# boost_0_8V_to_3_3V_v0_1.net
KiCad netlist of a schematic drawn in EasyEDA Pro
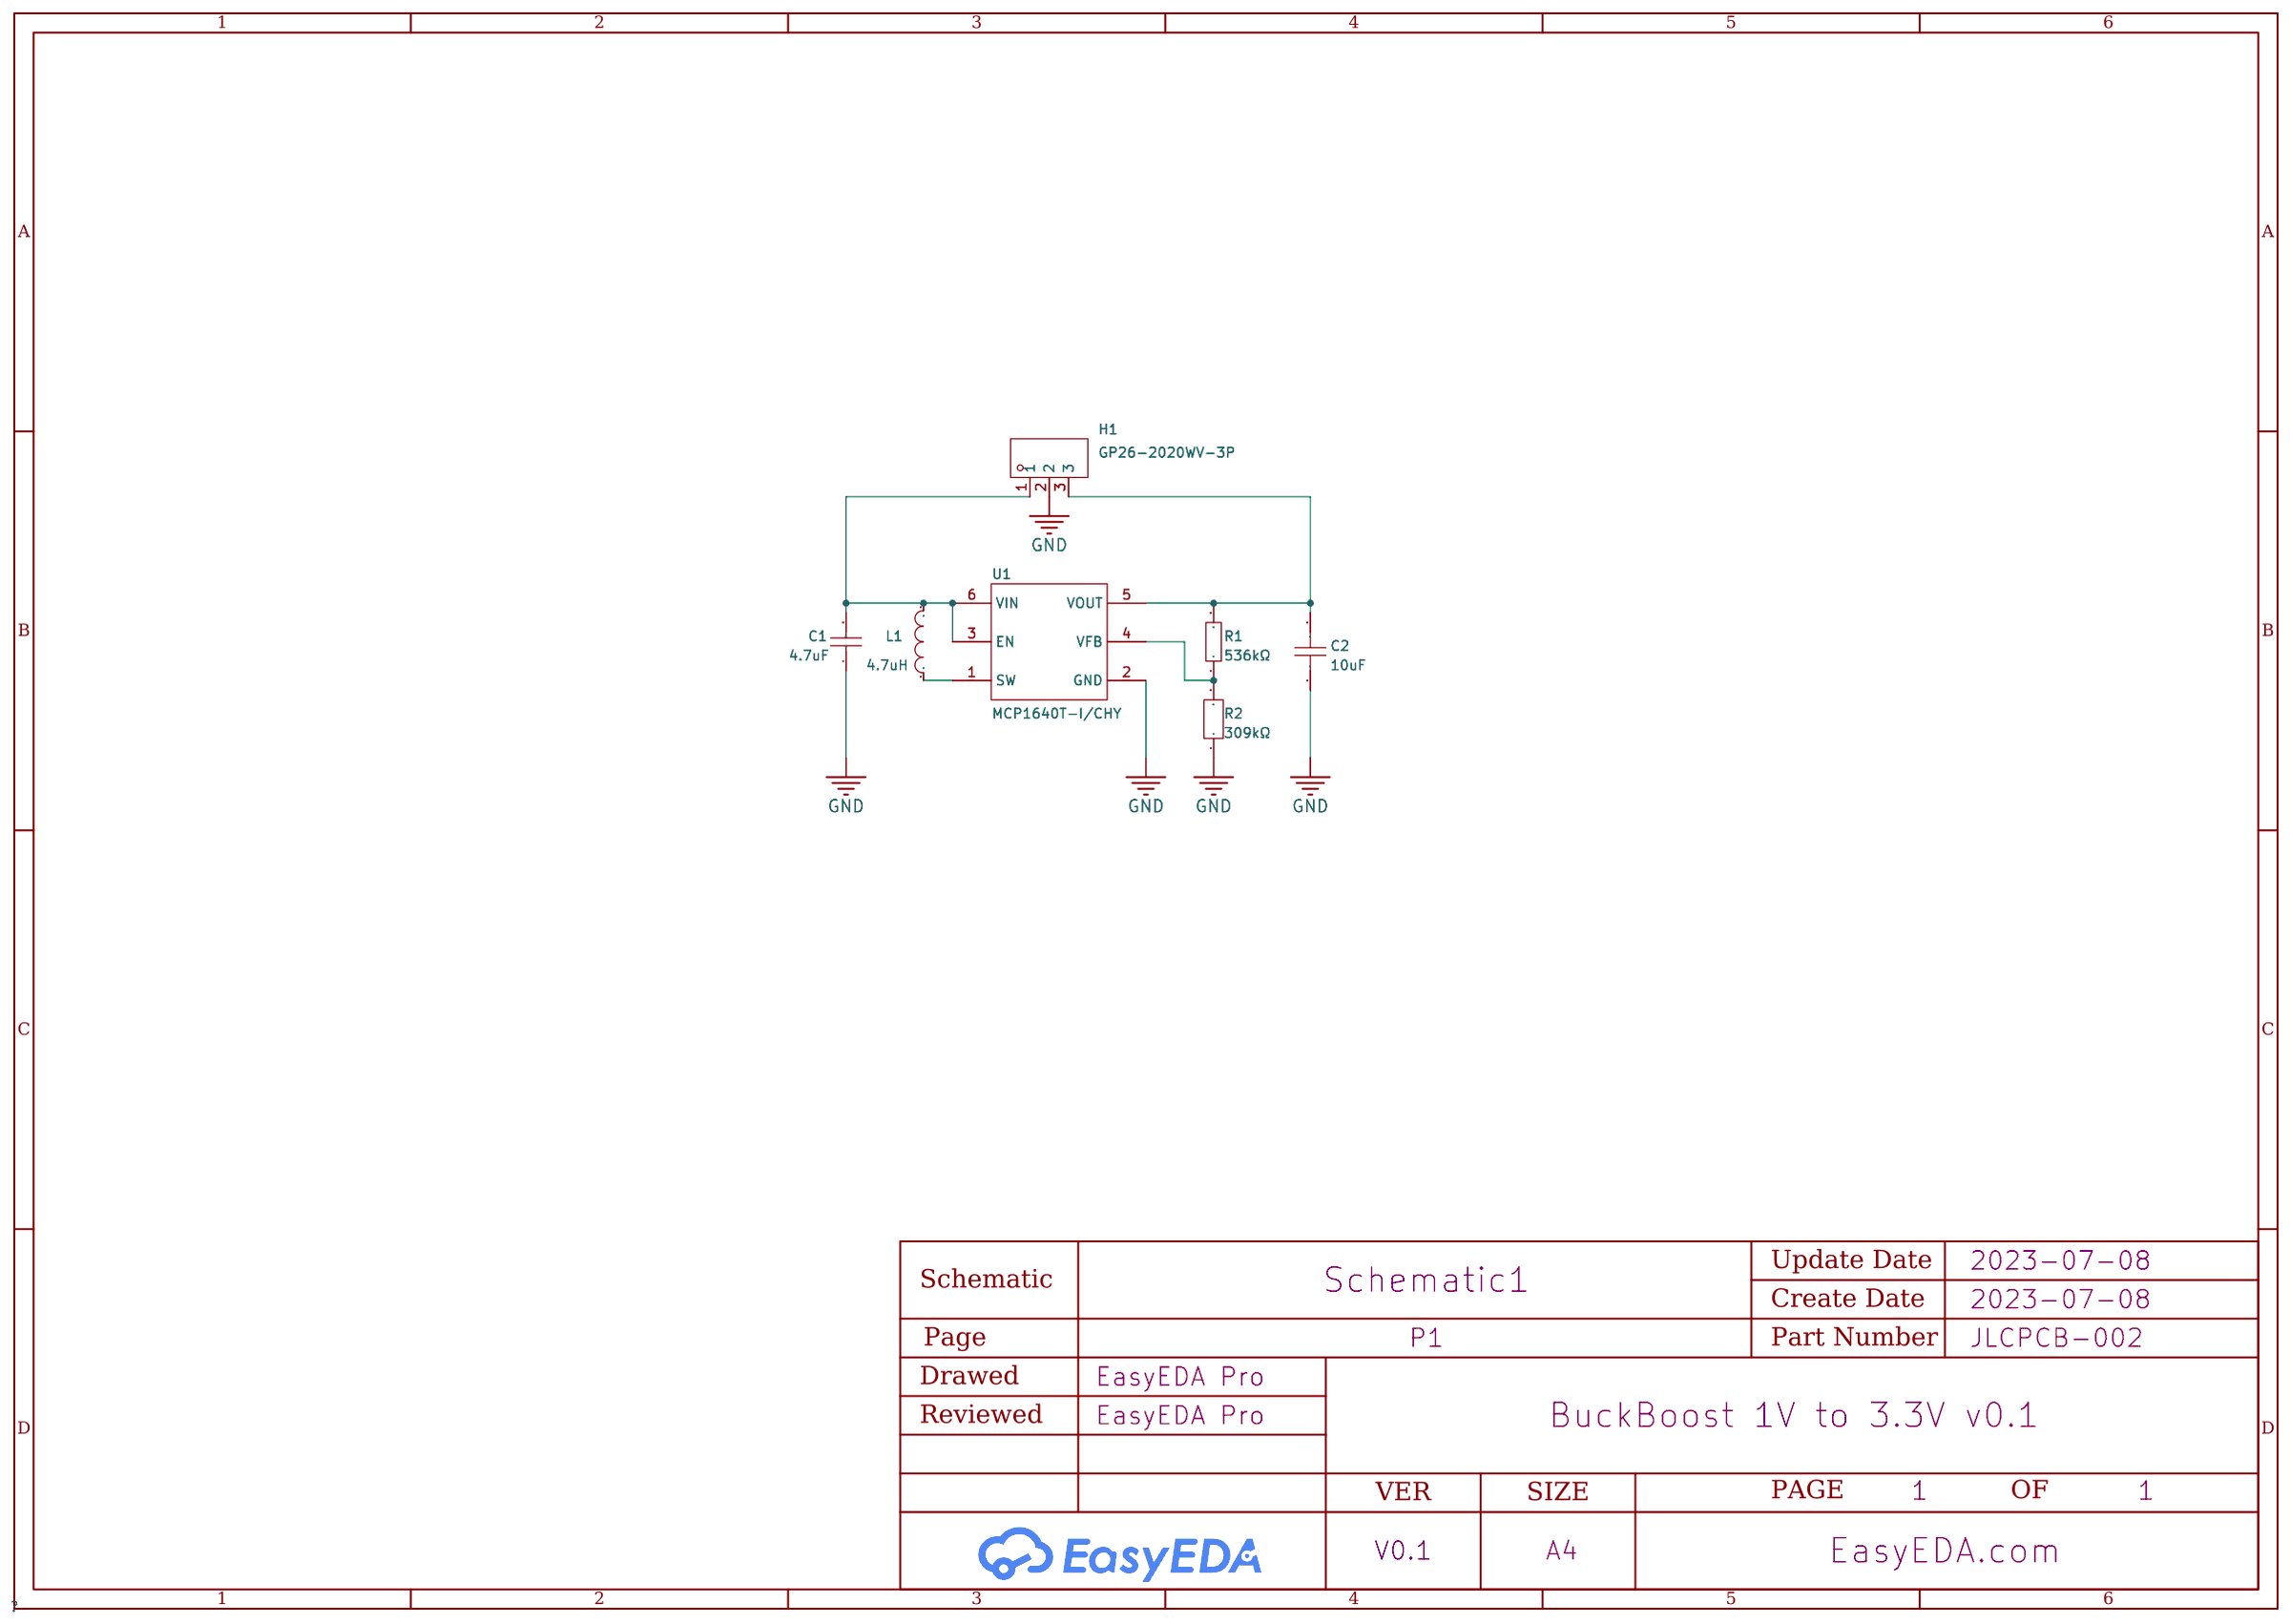
[diagram p0: schematic sheet]

(export (version "E")
  (design (tool "Eeschema 10.0.6"))
  (components
    (comp (ref "C1")
      (value "4.7uF")
      (footprint "easyedapro:C0603")
      (fields
        (field (name "Manufacturer Part") "CL10A475KO8NNNC")
        (field (name "Manufacturer") "SAMSUNG(三星)")
      )
      (libsource (lib "easyedapro") (part "CL10A475KO8NNNC"))
    )
    (comp (ref "C2")
      (value "10uF")
      (footprint "easyedapro:C0603")
      (fields
        (field (name "Manufacturer Part") "CL10A106KP8NNNC")
        (field (name "Manufacturer") "SAMSUNG(三星)")
      )
      (libsource (lib "easyedapro") (part "CL10A106KP8NNNC"))
    )
    (comp (ref "H1")
      (value "GP26-2020WV-3P")
      (footprint "easyedapro:HDR-TH_3P-P2.00-V-M")
      (fields (field (name "Manufacturer") "GEPU(歌普)"))
      (libsource (lib "easyedapro") (part "GP26-2020WV-3P"))
    )
    (comp (ref "L1")
      (value "4.7uH")
      (footprint "easyedapro:IND-SMD_L2.5-W1.8")
      (fields
        (field (name "Manufacturer Part") "CBC2518T4R7M")
        (field (name "Manufacturer") "TAIYO YUDEN(太诱)")
      )
      (libsource (lib "easyedapro") (part "CBC2518T4R7M"))
    )
    (comp (ref "R1")
      (value "536kΩ")
      (footprint "easyedapro:R0603")
      (fields (field (name "Manufacturer Part") "RTT035363FTP") (field (name "Manufacturer") "RALEC(旺诠)"))
      (libsource (lib "easyedapro") (part "RTT035363FTP"))
    )
    (comp (ref "R2")
      (value "309kΩ")
      (footprint "easyedapro:R0603")
      (fields (field (name "Manufacturer Part") "TD03G3093BT") (field (name "Manufacturer") "FH(风华)"))
      (libsource (lib "easyedapro") (part "TD03G3093BT"))
    )
    (comp (ref "U1")
      (value "MCP1640T-I/CHY")
      (footprint "easyedapro:SOT-23-6_L2.9-W1.6-P0.95-LS2.8-BR")
      (fields (field (name "Manufacturer") "MICROCHIP(美国微芯)"))
      (libsource (lib "easyedapro") (part "MCP1640T-I/CHY"))
    )
  )
  (nets
    (net (code "1") (name "GND") (class "Default")
      (node (ref "C1") (pin "1") (pinfunction "1_1") (pintype "input"))
      (node (ref "C2") (pin "1") (pinfunction "1_1") (pintype "input"))
      (node (ref "H1") (pin "2") (pinfunction "2_2") (pintype "input"))
      (node (ref "R2") (pin "1") (pinfunction "1_1") (pintype "input"))
      (node (ref "U1") (pin "2") (pinfunction "GND_2") (pintype "input"))
    )
    (net (code "2") (name "Net-(U1-EN)") (class "Default")
      (node (ref "C1") (pin "2") (pinfunction "2_2") (pintype "input"))
      (node (ref "H1") (pin "1") (pinfunction "1_1") (pintype "input"))
      (node (ref "L1") (pin "2") (pinfunction "2_2") (pintype "input"))
      (node (ref "U1") (pin "3") (pinfunction "EN_3") (pintype "input"))
      (node (ref "U1") (pin "6") (pinfunction "VIN_6") (pintype "input"))
    )
    (net (code "3") (name "Net-(U1-SW)") (class "Default")
      (node (ref "L1") (pin "1") (pinfunction "1_1") (pintype "input"))
      (node (ref "U1") (pin "1") (pinfunction "SW_1") (pintype "input"))
    )
    (net (code "4") (name "Net-(U1-VFB)") (class "Default")
      (node (ref "R1") (pin "1") (pinfunction "1_1") (pintype "input"))
      (node (ref "R2") (pin "2") (pinfunction "2_2") (pintype "input"))
      (node (ref "U1") (pin "4") (pinfunction "VFB_4") (pintype "input"))
    )
    (net (code "5") (name "Net-(U1-VOUT)") (class "Default")
      (node (ref "C2") (pin "2") (pinfunction "2_2") (pintype "input"))
      (node (ref "H1") (pin "3") (pinfunction "3_3") (pintype "input"))
      (node (ref "R1") (pin "2") (pinfunction "2_2") (pintype "input"))
      (node (ref "U1") (pin "5") (pinfunction "VOUT_5") (pintype "input"))
    )
  )
)
